# AIR_Control1_Relay_080116.net
KiCad netlist of a schematic drawn in Altium Designer
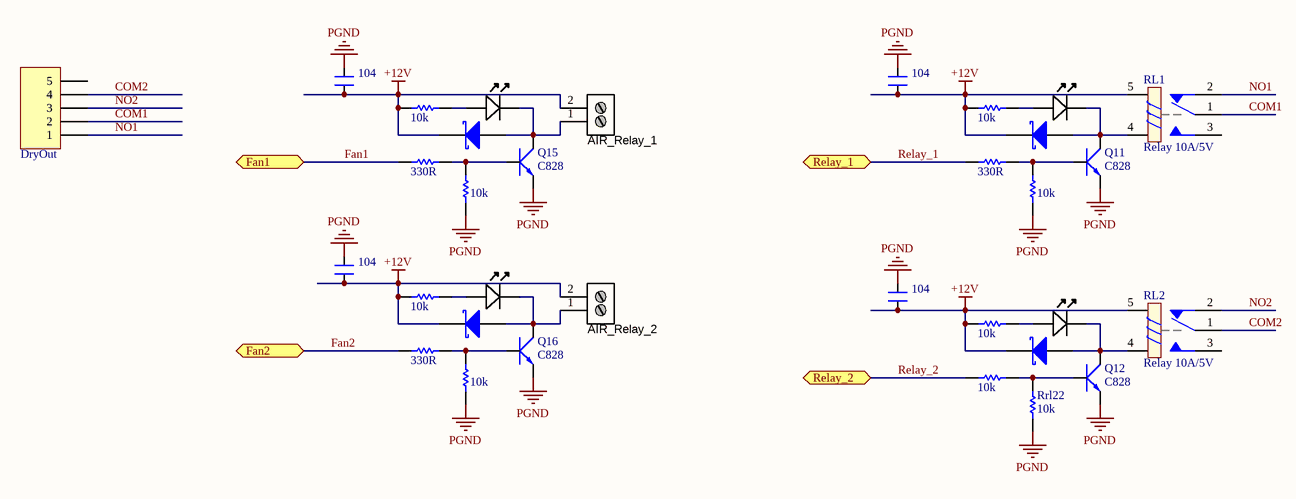
[diagram p0: AIR_Control1_Relay_080116.SchDoc]

(export (version "E")
  (design (tool "Eeschema 10.0.6"))
  (components
    (comp (ref "AIR_Relay_1")
      (value "Stackable ScrewTerm")
      (footprint "2P_PCB_ScrewTerm_200mil")
      (description "Terminal Block Screw Type THT 2-Position 3.81mm pitch")
      (libsource (lib "PBL - Connectors") (part "2P_ScrewTerm_90S_3.81MM"))
    )
    (comp (ref "AIR_Relay_2")
      (value "Stackable ScrewTerm")
      (footprint "2P_PCB_ScrewTerm_200mil")
      (description "Terminal Block Screw Type THT 2-Position 3.81mm pitch")
      (libsource (lib "PBL - Connectors") (part "2P_ScrewTerm_90S_3.81MM"))
    )
    (comp (ref "Crl1")
      (value "104")
      (footprint "CAPC2012N_F")
      (fields (field (name "Comment") "CAP NP"))
      (libsource (lib "Tuan") (part "CAP NP"))
    )
    (comp (ref "Crl2")
      (value "104")
      (footprint "CAPC2012N_F")
      (fields (field (name "Comment") "CAP NP"))
      (libsource (lib "Tuan") (part "CAP NP"))
    )
    (comp (ref "Crl5")
      (value "104")
      (footprint "CAPC2012N_F")
      (fields (field (name "Comment") "CAP NP"))
      (libsource (lib "Tuan") (part "CAP NP"))
    )
    (comp (ref "Crl6")
      (value "104")
      (footprint "CAPC2012N_F")
      (fields (field (name "Comment") "CAP NP"))
      (libsource (lib "Tuan") (part "CAP NP"))
    )
    (comp (ref "D11") (value "Diode") (footprint "DO-214AC") (libsource (lib "Tuan") (part "Diode")))
    (comp (ref "D12") (value "Diode") (footprint "DO-214AC") (libsource (lib "Tuan") (part "Diode")))
    (comp (ref "D15") (value "Diode") (footprint "DO-214AC") (libsource (lib "Tuan") (part "Diode")))
    (comp (ref "D16") (value "Diode") (footprint "DO-214AC") (libsource (lib "Tuan") (part "Diode")))
    (comp (ref "DryOut")
      (value "Header 5")
      (footprint "heromap:HDR1X5")
      (description "Header, 5-Pin")
      (fields (field (name "PUBLISHER") "Altium Limited"))
      (libsource (lib "heromap") (part "Header 5"))
    )
    (comp (ref "E1")
      (value "Blue")
      (footprint "LED-0805-A")
      (description "LED 0805 SMD Blue 100mcd 470nm")
      (libsource (lib "PBL - Light Sources") (part "LED_SMD_Blue_0805_100mcd"))
    )
    (comp (ref "E2")
      (value "Blue")
      (footprint "LED-0805-A")
      (description "LED 0805 SMD Blue 100mcd 470nm")
      (libsource (lib "PBL - Light Sources") (part "LED_SMD_Blue_0805_100mcd"))
    )
    (comp (ref "E5")
      (value "Blue")
      (footprint "LED-0805-A")
      (description "LED 0805 SMD Blue 100mcd 470nm")
      (libsource (lib "PBL - Light Sources") (part "LED_SMD_Blue_0805_100mcd"))
    )
    (comp (ref "E6")
      (value "Blue")
      (footprint "LED-0805-A")
      (description "LED 0805 SMD Blue 100mcd 470nm")
      (libsource (lib "PBL - Light Sources") (part "LED_SMD_Blue_0805_100mcd"))
    )
    (comp (ref "Q11")
      (value "C828")
      (footprint "SOT23 TOP")
      (description "Transistor C828 C1815....")
      (libsource (lib "Tuan") (part "NPN"))
    )
    (comp (ref "Q12")
      (value "C828")
      (footprint "SOT23 TOP")
      (description "Transistor C828 C1815....")
      (libsource (lib "Tuan") (part "NPN"))
    )
    (comp (ref "Q15")
      (value "C828")
      (footprint "SOT23 TOP")
      (description "Transistor C828 C1815....")
      (libsource (lib "Tuan") (part "NPN"))
    )
    (comp (ref "Q16")
      (value "C828")
      (footprint "SOT23 TOP")
      (description "Transistor C828 C1815....")
      (libsource (lib "Tuan") (part "NPN"))
    )
    (comp (ref "RL1")
      (value "Relay 10A/5V")
      (footprint "RL_5PIN")
      (description "Relay SPDT,10A - 12VDC 5 Pin")
      (libsource (lib "syhaunguyen") (part "Relay 1"))
    )
    (comp (ref "RL2")
      (value "Relay 10A/5V")
      (footprint "RL_5PIN")
      (description "Relay SPDT,10A - 12VDC 5 Pin")
      (libsource (lib "syhaunguyen") (part "Relay 1"))
    )
    (comp (ref "Rl52")
      (value "10k")
      (footprint "RESC1608N_ZERO")
      (fields (field (name "Comment") "Res"))
      (libsource (lib "Tuan") (part "Res"))
    )
    (comp (ref "Rrl11")
      (value "330R")
      (footprint "RESC1608N_ZERO")
      (fields (field (name "Comment") "Res"))
      (libsource (lib "Tuan") (part "Res"))
    )
    (comp (ref "Rrl12")
      (value "10k")
      (footprint "RESC1608N_ZERO")
      (fields (field (name "Comment") "Res"))
      (libsource (lib "Tuan") (part "Res"))
    )
    (comp (ref "Rrl13")
      (value "10k")
      (footprint "RESC1608N_ZERO")
      (fields (field (name "Comment") "Res"))
      (libsource (lib "Tuan") (part "Res"))
    )
    (comp (ref "Rrl21")
      (value "10k")
      (footprint "RESC1608N_ZERO")
      (fields (field (name "Comment") "Res"))
      (libsource (lib "Tuan") (part "Res"))
    )
    (comp (ref "Rrl22")
      (value "10k")
      (footprint "RESC1608N_ZERO")
      (fields (field (name "Comment") "Res"))
      (libsource (lib "Tuan") (part "Res"))
    )
    (comp (ref "Rrl23")
      (value "10k")
      (footprint "RESC1608N_ZERO")
      (fields (field (name "Comment") "Res"))
      (libsource (lib "Tuan") (part "Res"))
    )
    (comp (ref "Rrl51")
      (value "330R")
      (footprint "RESC1608N_ZERO")
      (fields (field (name "Comment") "Res"))
      (libsource (lib "Tuan") (part "Res"))
    )
    (comp (ref "Rrl53")
      (value "10k")
      (footprint "RESC1608N_ZERO")
      (fields (field (name "Comment") "Res"))
      (libsource (lib "Tuan") (part "Res"))
    )
    (comp (ref "Rrl61")
      (value "330R")
      (footprint "RESC1608N_ZERO")
      (fields (field (name "Comment") "Res"))
      (libsource (lib "Tuan") (part "Res"))
    )
    (comp (ref "Rrl62")
      (value "10k")
      (footprint "RESC1608N_ZERO")
      (fields (field (name "Comment") "Res"))
      (libsource (lib "Tuan") (part "Res"))
    )
    (comp (ref "Rrl63")
      (value "10k")
      (footprint "RESC1608N_ZERO")
      (fields (field (name "Comment") "Res"))
      (libsource (lib "Tuan") (part "Res"))
    )
  )
  (nets
    (net (code "1") (name "+12V") (class "Default")
      (node (ref "AIR_Relay_1") (pin "2") (pinfunction "2_2") (pintype "passive"))
      (node (ref "AIR_Relay_2") (pin "2") (pinfunction "2_2") (pintype "passive"))
      (node (ref "Crl1") (pin "1") (pinfunction "1_1") (pintype "passive"))
      (node (ref "Crl2") (pin "1") (pinfunction "1_1") (pintype "passive"))
      (node (ref "Crl5") (pin "1") (pinfunction "1_1") (pintype "passive"))
      (node (ref "Crl6") (pin "1") (pinfunction "1_1") (pintype "passive"))
      (node (ref "D11") (pin "2") (pinfunction "K_2") (pintype "passive"))
      (node (ref "D12") (pin "2") (pinfunction "K_2") (pintype "passive"))
      (node (ref "D15") (pin "2") (pinfunction "K_2") (pintype "passive"))
      (node (ref "D16") (pin "2") (pinfunction "K_2") (pintype "passive"))
      (node (ref "RL1") (pin "5") (pinfunction "5_5") (pintype "passive"))
      (node (ref "RL2") (pin "5") (pinfunction "5_5") (pintype "passive"))
      (node (ref "Rrl13") (pin "2") (pinfunction "2_2") (pintype "passive"))
      (node (ref "Rrl23") (pin "2") (pinfunction "2_2") (pintype "passive"))
      (node (ref "Rrl53") (pin "2") (pinfunction "2_2") (pintype "passive"))
      (node (ref "Rrl63") (pin "2") (pinfunction "2_2") (pintype "passive"))
    )
    (net (code "2") (name "/COM1") (class "Default")
      (node (ref "DryOut") (pin "2") (pinfunction "2_2") (pintype "passive"))
      (node (ref "RL1") (pin "1") (pinfunction "1_1") (pintype "passive"))
    )
    (net (code "3") (name "/COM2") (class "Default")
      (node (ref "DryOut") (pin "4") (pinfunction "4_4") (pintype "passive"))
      (node (ref "RL2") (pin "1") (pinfunction "1_1") (pintype "passive"))
    )
    (net (code "4") (name "/Fan1") (class "Default")
      (node (ref "Rrl51") (pin "1") (pinfunction "1_1") (pintype "passive"))
    )
    (net (code "5") (name "/Fan2") (class "Default")
      (node (ref "Rrl61") (pin "1") (pinfunction "1_1") (pintype "passive"))
    )
    (net (code "6") (name "/NO1") (class "Default")
      (node (ref "DryOut") (pin "1") (pinfunction "1_1") (pintype "passive"))
      (node (ref "RL1") (pin "2") (pinfunction "2_2") (pintype "passive"))
    )
    (net (code "7") (name "/NO2") (class "Default")
      (node (ref "DryOut") (pin "3") (pinfunction "3_3") (pintype "passive"))
      (node (ref "RL2") (pin "2") (pinfunction "2_2") (pintype "passive"))
    )
    (net (code "8") (name "/Relay_1") (class "Default")
      (node (ref "Rrl11") (pin "1") (pinfunction "1_1") (pintype "passive"))
    )
    (net (code "9") (name "/Relay_2") (class "Default")
      (node (ref "Rrl21") (pin "1") (pinfunction "1_1") (pintype "passive"))
    )
    (net (code "10") (name "Net-(D11-A)") (class "Default")
      (node (ref "D11") (pin "1") (pinfunction "A_1") (pintype "passive"))
      (node (ref "E1") (pin "K") (pinfunction "K_K") (pintype "passive"))
      (node (ref "Q11") (pin "2") (pinfunction "C_2") (pintype "passive"))
      (node (ref "RL1") (pin "4") (pinfunction "4_4") (pintype "passive"))
    )
    (net (code "11") (name "Net-(D12-A)") (class "Default")
      (node (ref "D12") (pin "1") (pinfunction "A_1") (pintype "passive"))
      (node (ref "E2") (pin "K") (pinfunction "K_K") (pintype "passive"))
      (node (ref "Q12") (pin "2") (pinfunction "C_2") (pintype "passive"))
      (node (ref "RL2") (pin "4") (pinfunction "4_4") (pintype "passive"))
    )
    (net (code "12") (name "Net-(D15-A)") (class "Default")
      (node (ref "AIR_Relay_1") (pin "1") (pinfunction "1_1") (pintype "passive"))
      (node (ref "D15") (pin "1") (pinfunction "A_1") (pintype "passive"))
      (node (ref "E5") (pin "K") (pinfunction "K_K") (pintype "passive"))
      (node (ref "Q15") (pin "2") (pinfunction "C_2") (pintype "passive"))
    )
    (net (code "13") (name "Net-(D16-A)") (class "Default")
      (node (ref "AIR_Relay_2") (pin "1") (pinfunction "1_1") (pintype "passive"))
      (node (ref "D16") (pin "1") (pinfunction "A_1") (pintype "passive"))
      (node (ref "E6") (pin "K") (pinfunction "K_K") (pintype "passive"))
      (node (ref "Q16") (pin "2") (pinfunction "C_2") (pintype "passive"))
    )
    (net (code "14") (name "Net-(E1-PadA)") (class "Default")
      (node (ref "E1") (pin "A") (pinfunction "A_A") (pintype "passive"))
      (node (ref "Rrl13") (pin "1") (pinfunction "1_1") (pintype "passive"))
    )
    (net (code "15") (name "Net-(E2-PadA)") (class "Default")
      (node (ref "E2") (pin "A") (pinfunction "A_A") (pintype "passive"))
      (node (ref "Rrl23") (pin "1") (pinfunction "1_1") (pintype "passive"))
    )
    (net (code "16") (name "Net-(E5-PadA)") (class "Default")
      (node (ref "E5") (pin "A") (pinfunction "A_A") (pintype "passive"))
      (node (ref "Rrl53") (pin "1") (pinfunction "1_1") (pintype "passive"))
    )
    (net (code "17") (name "Net-(E6-PadA)") (class "Default")
      (node (ref "E6") (pin "A") (pinfunction "A_A") (pintype "passive"))
      (node (ref "Rrl63") (pin "1") (pinfunction "1_1") (pintype "passive"))
    )
    (net (code "18") (name "Net-(Q11-B)") (class "Default")
      (node (ref "Q11") (pin "1") (pinfunction "B_1") (pintype "passive"))
      (node (ref "Rrl11") (pin "2") (pinfunction "2_2") (pintype "passive"))
      (node (ref "Rrl12") (pin "2") (pinfunction "2_2") (pintype "passive"))
    )
    (net (code "19") (name "Net-(Q12-B)") (class "Default")
      (node (ref "Q12") (pin "1") (pinfunction "B_1") (pintype "passive"))
      (node (ref "Rrl21") (pin "2") (pinfunction "2_2") (pintype "passive"))
      (node (ref "Rrl22") (pin "2") (pinfunction "2_2") (pintype "passive"))
    )
    (net (code "20") (name "Net-(Q15-B)") (class "Default")
      (node (ref "Q15") (pin "1") (pinfunction "B_1") (pintype "passive"))
      (node (ref "Rl52") (pin "2") (pinfunction "2_2") (pintype "passive"))
      (node (ref "Rrl51") (pin "2") (pinfunction "2_2") (pintype "passive"))
    )
    (net (code "21") (name "Net-(Q16-B)") (class "Default")
      (node (ref "Q16") (pin "1") (pinfunction "B_1") (pintype "passive"))
      (node (ref "Rrl61") (pin "2") (pinfunction "2_2") (pintype "passive"))
      (node (ref "Rrl62") (pin "2") (pinfunction "2_2") (pintype "passive"))
    )
    (net (code "22") (name "PGND") (class "Default")
      (node (ref "Crl1") (pin "2") (pinfunction "2_2") (pintype "passive"))
      (node (ref "Crl2") (pin "2") (pinfunction "2_2") (pintype "passive"))
      (node (ref "Crl5") (pin "2") (pinfunction "2_2") (pintype "passive"))
      (node (ref "Crl6") (pin "2") (pinfunction "2_2") (pintype "passive"))
      (node (ref "Q11") (pin "3") (pinfunction "E_3") (pintype "passive"))
      (node (ref "Q12") (pin "3") (pinfunction "E_3") (pintype "passive"))
      (node (ref "Q15") (pin "3") (pinfunction "E_3") (pintype "passive"))
      (node (ref "Q16") (pin "3") (pinfunction "E_3") (pintype "passive"))
      (node (ref "Rl52") (pin "1") (pinfunction "1_1") (pintype "passive"))
      (node (ref "Rrl12") (pin "1") (pinfunction "1_1") (pintype "passive"))
      (node (ref "Rrl22") (pin "1") (pinfunction "1_1") (pintype "passive"))
      (node (ref "Rrl62") (pin "1") (pinfunction "1_1") (pintype "passive"))
    )
    (net (code "23") (name "unconnected-(DryOut-Pad5)") (class "Default")
      (node (ref "DryOut") (pin "5") (pinfunction "5_5") (pintype "passive"))
    )
    (net (code "24") (name "unconnected-(RL1-Pad3)") (class "Default")
      (node (ref "RL1") (pin "3") (pinfunction "3_3") (pintype "passive"))
    )
    (net (code "25") (name "unconnected-(RL2-Pad3)") (class "Default")
      (node (ref "RL2") (pin "3") (pinfunction "3_3") (pintype "passive"))
    )
  )
)
